# BAT___PROTECTOR.net
KiCad netlist of a schematic drawn in Altium Designer
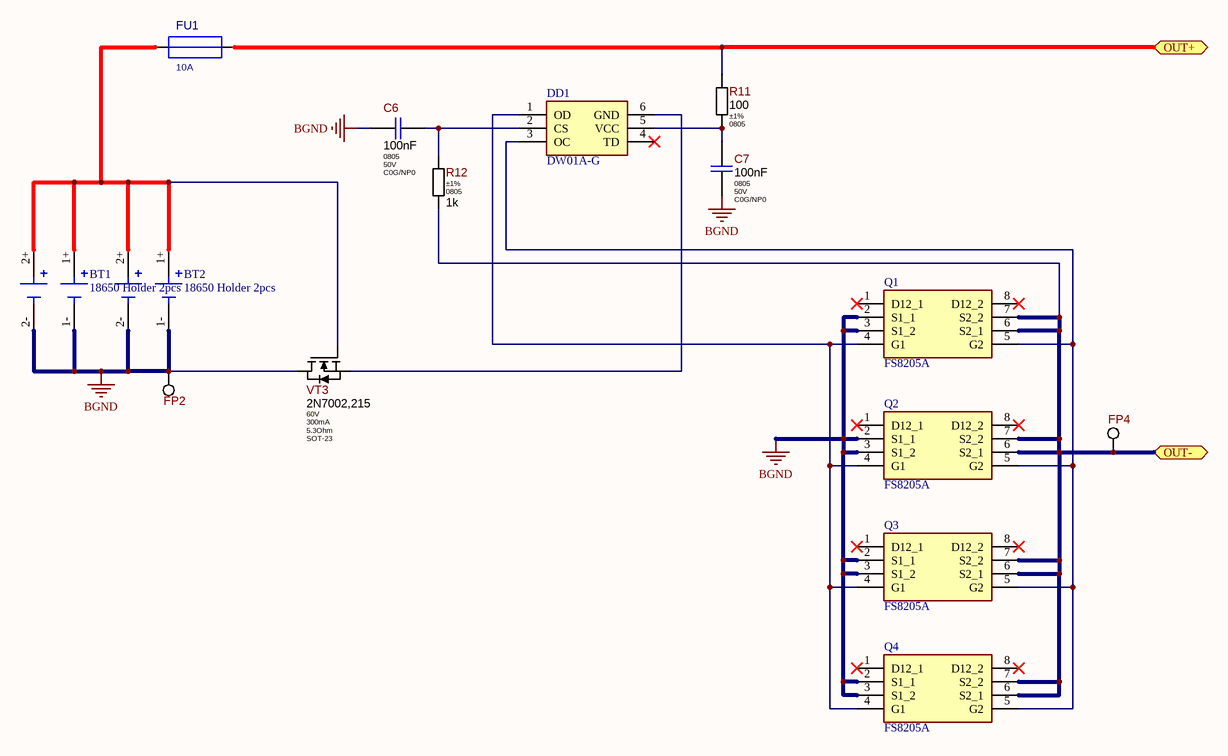
[diagram p0: BAT_&_PROTECTOR.SchDoc]

(export (version "E")
  (design (tool "Eeschema 10.0.6"))
  (components
    (comp (ref "BT1")
      (value "18650 Holder 2pcs")
      (footprint "BAT_BK-18650-PC4")
      (description "Battery Holder (Open) 18650 2 Cell PC Pin")
      (fields (field (name "MP") "BK-18650-PC4"))
      (libsource (lib "vitech_lib") (part "18650 Holder 2pcs"))
    )
    (comp (ref "BT2")
      (value "18650 Holder 2pcs")
      (footprint "BAT_BK-18650-PC4")
      (description "Battery Holder (Open) 18650 2 Cell PC Pin")
      (fields (field (name "MP") "BK-18650-PC4"))
      (libsource (lib "vitech_lib") (part "18650 Holder 2pcs"))
    )
    (comp (ref "C6")
      (value "100nF")
      (footprint "C_CERAMIC_0805_HI")
      (fields
        (field (name "PART NUMBER") "**")
        (field (name "MANUFACTURER") "Hitano")
        (field (name "TOLERANCE") "±5%")
        (field (name "PACKAGE") "0805")
        (field (name "VOLTAGE") "50V")
        (field (name "DIELECTRIC TYPE") "C0G/NP0")
      )
      (libsource (lib "vitech_capacitors") (part "CERAMIC_0805"))
    )
    (comp (ref "C7")
      (value "100nF")
      (footprint "C_CERAMIC_0805_HI")
      (fields
        (field (name "PART NUMBER") "**")
        (field (name "MANUFACTURER") "Hitano")
        (field (name "TOLERANCE") "±5%")
        (field (name "PACKAGE") "0805")
        (field (name "VOLTAGE") "50V")
        (field (name "DIELECTRIC TYPE") "C0G/NP0")
      )
      (libsource (lib "vitech_capacitors") (part "CERAMIC_0805"))
    )
    (comp (ref "DD1")
      (value "DW01A-G")
      (footprint "DW01A-G")
      (description "One Cell Lithium-ion/Polymer Battery Protection IC")
      (libsource (lib "vitech_ic") (part "DW01A-G"))
    )
    (comp (ref "FP2")
      (value "PAD-1.45mm")
      (footprint "PAD-1.45mm")
      (description "1.45mm Pad for Plug-In or Receptacle")
      (fields (field (name "MANUFACTURER") "NONE"))
      (libsource (lib "probetools") (part "PAD-1.45mm"))
    )
    (comp (ref "FP4")
      (value "PAD-1.45mm")
      (footprint "PAD-1.45mm")
      (description "1.45mm Pad for Plug-In or Receptacle")
      (fields (field (name "MANUFACTURER") "NONE"))
      (libsource (lib "probetools") (part "PAD-1.45mm"))
    )
    (comp (ref "FU1")
      (value "10A")
      (footprint "FU_2410_6.0x2.5x2.5mm_v2")
      (description "Medium Blow Fuse 65V 15A SMD 2410")
      (fields (field (name "MANUFACTURER") "BEL FUSE") (field (name "PART NUMBER") "0679L9100-01"))
      (libsource (lib "Passive") (part "FUSE_SMD_2410_v2"))
    )
    (comp (ref "Q1")
      (value "FS8205A")
      (footprint "FS8205A")
      (description "Dual N-Channel Enahncement Mode Power MOSFET")
      (libsource (lib "vitech_lib") (part "FS8205A"))
    )
    (comp (ref "Q2")
      (value "FS8205A")
      (footprint "FS8205A")
      (description "Dual N-Channel Enahncement Mode Power MOSFET")
      (libsource (lib "vitech_lib") (part "FS8205A"))
    )
    (comp (ref "Q3")
      (value "FS8205A")
      (footprint "FS8205A")
      (description "Dual N-Channel Enahncement Mode Power MOSFET")
      (libsource (lib "vitech_lib") (part "FS8205A"))
    )
    (comp (ref "Q4")
      (value "FS8205A")
      (footprint "FS8205A")
      (description "Dual N-Channel Enahncement Mode Power MOSFET")
      (libsource (lib "vitech_lib") (part "FS8205A"))
    )
    (comp (ref "R11")
      (value "100")
      (footprint "R_ANY_CHIP_0805_MED")
      (description "100 Ohms ±1%, 1/8W 0805 Thick Film Resistor")
      (fields
        (field (name "TOLERANCE") "±1%")
        (field (name "PACKAGE") "0805")
        (field (name "PART NUMBER") "RC0805FR-07120RL")
        (field (name "MANUFACTURER") "Yageo")
      )
      (libsource (lib "resistors") (part "RC0805FR-07120RL"))
    )
    (comp (ref "R12")
      (value "1k")
      (footprint "R_ANY_CHIP_0805_MED")
      (description "1 kOhms ±1%, 1/8W 0805 Thick Film Resistor")
      (fields
        (field (name "TOLERANCE") "±1%")
        (field (name "PACKAGE") "0805")
        (field (name "PART NUMBER") "RC0805FR-071KL")
        (field (name "MANUFACTURER") "Yageo")
      )
      (libsource (lib "resistors") (part "RC0805FR-071KL"))
    )
    (comp (ref "VT3")
      (value "2N7002,215")
      (footprint "SOT-23_MED")
      (description "60V, 300mA max N-Channel Trench MOSFET, 3.8Ohm @ Vgs = 4.5V")
      (fields
        (field (name "PART NUMBER") "2N7002,215")
        (field (name "VDS") "60V")
        (field (name "ID") "300mA")
        (field (name "RDS") "5.3Ohm")
        (field (name "PACKAGE") "SOT-23")
        (field (name "MANUFACTURER") "Nexperia USA")
      )
      (libsource (lib "transistors") (part "2N7002,215"))
    )
  )
  (nets
    (net (code "1") (name "/OUT+") (class "Default")
      (node (ref "FU1") (pin "2") (pinfunction "2_2") (pintype "passive"))
      (node (ref "R11") (pin "2") (pintype "passive"))
    )
    (net (code "2") (name "/OUT-") (class "Default")
      (node (ref "FP4") (pin "1") (pintype "passive"))
      (node (ref "Q1") (pin "6") (pinfunction "S2_1_6") (pintype "passive"))
      (node (ref "Q1") (pin "7") (pinfunction "S2_2_7") (pintype "passive"))
      (node (ref "Q2") (pin "6") (pinfunction "S2_1_6") (pintype "passive"))
      (node (ref "Q2") (pin "7") (pinfunction "S2_2_7") (pintype "passive"))
      (node (ref "Q3") (pin "6") (pinfunction "S2_1_6") (pintype "passive"))
      (node (ref "Q3") (pin "7") (pinfunction "S2_2_7") (pintype "passive"))
      (node (ref "Q4") (pin "6") (pinfunction "S2_1_6") (pintype "passive"))
      (node (ref "Q4") (pin "7") (pinfunction "S2_2_7") (pintype "passive"))
      (node (ref "R12") (pin "1") (pintype "passive"))
    )
    (net (code "3") (name "BGND") (class "Default")
      (node (ref "BT1") (pin "1-") (pinfunction "1-_1-") (pintype "passive"))
      (node (ref "BT1") (pin "2-") (pinfunction "2-_2-") (pintype "passive"))
      (node (ref "BT2") (pin "1-") (pinfunction "1-_1-") (pintype "passive"))
      (node (ref "BT2") (pin "2-") (pinfunction "2-_2-") (pintype "passive"))
      (node (ref "C6") (pin "1") (pinfunction "1_1") (pintype "passive"))
      (node (ref "C7") (pin "2") (pinfunction "2_2") (pintype "passive"))
      (node (ref "FP2") (pin "1") (pintype "passive"))
      (node (ref "Q1") (pin "2") (pinfunction "S1_1_2") (pintype "passive"))
      (node (ref "Q1") (pin "3") (pinfunction "S1_2_3") (pintype "passive"))
      (node (ref "Q2") (pin "2") (pinfunction "S1_1_2") (pintype "passive"))
      (node (ref "Q2") (pin "3") (pinfunction "S1_2_3") (pintype "passive"))
      (node (ref "Q3") (pin "2") (pinfunction "S1_1_2") (pintype "passive"))
      (node (ref "Q3") (pin "3") (pinfunction "S1_2_3") (pintype "passive"))
      (node (ref "Q4") (pin "2") (pinfunction "S1_1_2") (pintype "passive"))
      (node (ref "Q4") (pin "3") (pinfunction "S1_2_3") (pintype "passive"))
      (node (ref "VT3") (pin "3") (pinfunction "D_3") (pintype "passive"))
    )
    (net (code "4") (name "Net-(DD1-CS)") (class "Default")
      (node (ref "C6") (pin "2") (pinfunction "2_2") (pintype "passive"))
      (node (ref "DD1") (pin "2") (pinfunction "CS_2") (pintype "passive"))
      (node (ref "R12") (pin "2") (pintype "passive"))
    )
    (net (code "5") (name "Net-(DD1-GND)") (class "Default")
      (node (ref "DD1") (pin "6") (pinfunction "GND_6") (pintype "passive"))
      (node (ref "VT3") (pin "2") (pinfunction "S_2") (pintype "passive"))
    )
    (net (code "6") (name "Net-(DD1-OC)") (class "Default")
      (node (ref "DD1") (pin "3") (pinfunction "OC_3") (pintype "passive"))
      (node (ref "Q1") (pin "5") (pinfunction "G2_5") (pintype "passive"))
      (node (ref "Q2") (pin "5") (pinfunction "G2_5") (pintype "passive"))
      (node (ref "Q3") (pin "5") (pinfunction "G2_5") (pintype "passive"))
      (node (ref "Q4") (pin "5") (pinfunction "G2_5") (pintype "passive"))
    )
    (net (code "7") (name "Net-(DD1-OD)") (class "Default")
      (node (ref "DD1") (pin "1") (pinfunction "OD_1") (pintype "passive"))
      (node (ref "Q1") (pin "4") (pinfunction "G1_4") (pintype "passive"))
      (node (ref "Q2") (pin "4") (pinfunction "G1_4") (pintype "passive"))
      (node (ref "Q3") (pin "4") (pinfunction "G1_4") (pintype "passive"))
      (node (ref "Q4") (pin "4") (pinfunction "G1_4") (pintype "passive"))
    )
    (net (code "8") (name "Net-(DD1-VCC)") (class "Default")
      (node (ref "C7") (pin "1") (pinfunction "1_1") (pintype "passive"))
      (node (ref "DD1") (pin "5") (pinfunction "VCC_5") (pintype "passive"))
      (node (ref "R11") (pin "1") (pintype "passive"))
    )
    (net (code "9") (name "Net-(VT3-G)") (class "Default")
      (node (ref "BT1") (pin "1+") (pinfunction "1+_1+") (pintype "passive"))
      (node (ref "BT1") (pin "2+") (pinfunction "2+_2+") (pintype "passive"))
      (node (ref "BT2") (pin "1+") (pinfunction "1+_1+") (pintype "passive"))
      (node (ref "BT2") (pin "2+") (pinfunction "2+_2+") (pintype "passive"))
      (node (ref "FU1") (pin "1") (pinfunction "1_1") (pintype "passive"))
      (node (ref "VT3") (pin "1") (pinfunction "G_1") (pintype "passive"))
    )
    (net (code "10") (name "unconnected-(DD1-TD-Pad4)") (class "Default")
      (node (ref "DD1") (pin "4") (pinfunction "TD_4") (pintype "passive+no_connect"))
    )
    (net (code "11") (name "unconnected-(Q1-D12_1-Pad1)") (class "Default")
      (node (ref "Q1") (pin "1") (pinfunction "D12_1_1") (pintype "passive+no_connect"))
    )
    (net (code "12") (name "unconnected-(Q1-D12_2-Pad8)") (class "Default")
      (node (ref "Q1") (pin "8") (pinfunction "D12_2_8") (pintype "passive+no_connect"))
    )
    (net (code "13") (name "unconnected-(Q2-D12_1-Pad1)") (class "Default")
      (node (ref "Q2") (pin "1") (pinfunction "D12_1_1") (pintype "passive+no_connect"))
    )
    (net (code "14") (name "unconnected-(Q2-D12_2-Pad8)") (class "Default")
      (node (ref "Q2") (pin "8") (pinfunction "D12_2_8") (pintype "passive+no_connect"))
    )
    (net (code "15") (name "unconnected-(Q3-D12_1-Pad1)") (class "Default")
      (node (ref "Q3") (pin "1") (pinfunction "D12_1_1") (pintype "passive+no_connect"))
    )
    (net (code "16") (name "unconnected-(Q3-D12_2-Pad8)") (class "Default")
      (node (ref "Q3") (pin "8") (pinfunction "D12_2_8") (pintype "passive+no_connect"))
    )
    (net (code "17") (name "unconnected-(Q4-D12_1-Pad1)") (class "Default")
      (node (ref "Q4") (pin "1") (pinfunction "D12_1_1") (pintype "passive+no_connect"))
    )
    (net (code "18") (name "unconnected-(Q4-D12_2-Pad8)") (class "Default")
      (node (ref "Q4") (pin "8") (pinfunction "D12_2_8") (pintype "passive+no_connect"))
    )
  )
)
